# ScreenBase.net
KiCad netlist of a schematic drawn in Altium Designer
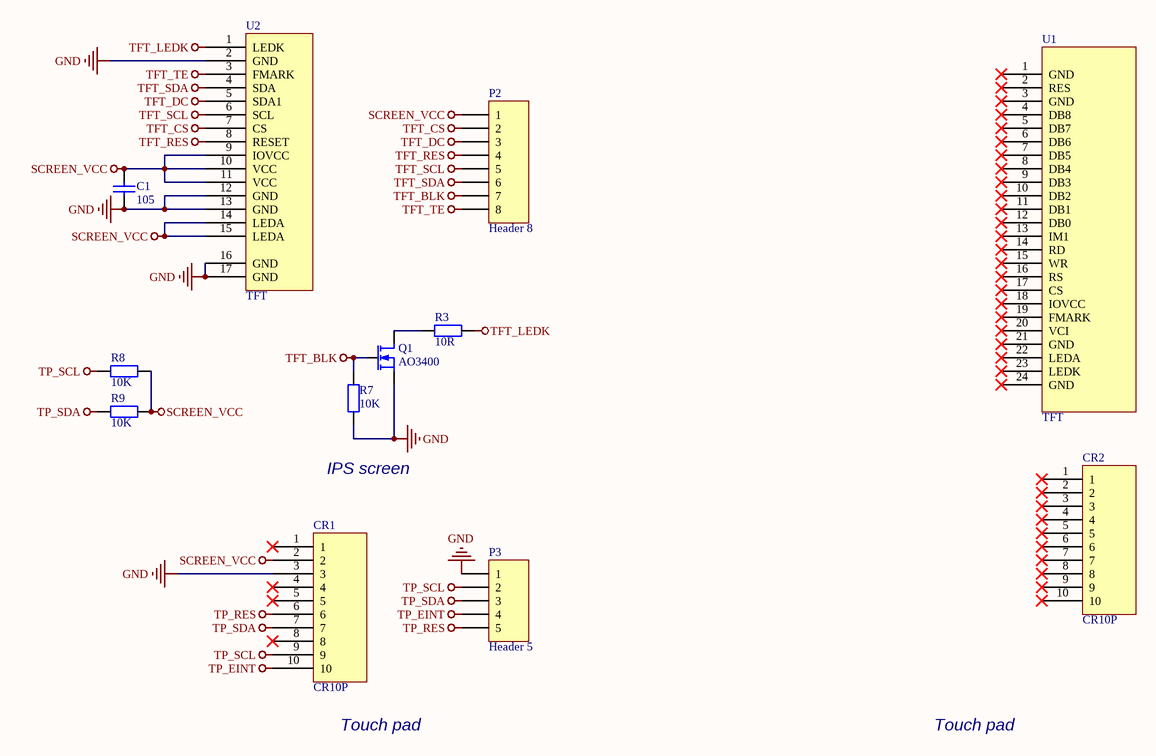
[diagram p0: ScreenBase.SchDoc]

(export (version "E")
  (design (tool "Eeschema 10.0.6"))
  (components
    (comp (ref "C1")
      (value "105")
      (footprint "电容_C0603")
      (fields (field (name "C") "105"))
      (libsource (lib "元件库") (part "cap"))
    )
    (comp (ref "CR1")
      (value "CR10P")
      (footprint "TriggersLib:CONN RCPT 10POS 0.4MM")
      (description "板对板连接器")
      (libsource (lib "TriggersLib") (part "CONN RCPT 10P"))
    )
    (comp (ref "CR2")
      (value "CR10P")
      (footprint "TriggersLib:CONN RCPT 10POS 0.4MM")
      (description "板对板连接器")
      (libsource (lib "TriggersLib") (part "CONN RCPT 10P"))
    )
    (comp (ref "P2")
      (value "Header 8")
      (footprint "HDR1X8")
      (description "Header, 8-Pin")
      (fields (field (name "PUBLISHER") "Altium Limited"))
      (libsource (lib "Miscellaneous Connectors") (part "Header 8"))
    )
    (comp (ref "P3")
      (value "Header 5")
      (footprint "HDR1X5")
      (description "Header, 5-Pin")
      (fields (field (name "PUBLISHER") "Altium Limited"))
      (libsource (lib "Miscellaneous Connectors") (part "Header 5"))
    )
    (comp (ref "Q1")
      (value "AO3400")
      (footprint "MOS_SOT-23")
      (fields (field (name "_MODEL") "AO3400"))
      (libsource (lib "元件库") (part "MOSFET-N"))
    )
    (comp (ref "R3")
      (value "10R")
      (footprint "电阻_R0603")
      (fields (field (name "_VALUE") "10R"))
      (libsource (lib "") (part "Res_1"))
    )
    (comp (ref "R7")
      (value "10K")
      (footprint "电阻_R0603")
      (fields (field (name "_VALUE") "10K"))
      (libsource (lib "") (part "Res_2"))
    )
    (comp (ref "R8")
      (value "10K")
      (footprint "电阻_R0603")
      (fields (field (name "_VALUE") "10K"))
      (libsource (lib "元件库") (part "Res"))
    )
    (comp (ref "R9")
      (value "10K")
      (footprint "电阻_R0603")
      (fields (field (name "_VALUE") "10K"))
      (libsource (lib "元件库") (part "Res"))
    )
    (comp (ref "U1")
      (value "TFT")
      (footprint "TriggersLib:CONN-SMD_DF37NC-24DS-0.4V(51)")
      (libsource (lib "TriggersLib") (part "TFT_IPS_8Bit_1.54_240*240"))
    )
    (comp (ref "U2")
      (value "TFT")
      (footprint "TriggersLib:FPC-0.30mm-15P")
      (description "IPS电容式触摸屏")
      (libsource (lib "TriggersLib") (part "TFT_IPS1-1.54寸240*240-AML015410V1"))
    )
  )
  (nets
    (net (code "1") (name "GND") (class "Default")
      (node (ref "C1") (pin "2") (pinfunction "2_2") (pintype "passive"))
      (node (ref "CR1") (pin "3") (pinfunction "3_3") (pintype "passive"))
      (node (ref "P3") (pin "1") (pinfunction "1_1") (pintype "passive"))
      (node (ref "Q1") (pin "3") (pinfunction "S_3") (pintype "passive"))
      (node (ref "R7") (pin "1") (pinfunction "1_1") (pintype "passive"))
      (node (ref "U2") (pin "12") (pinfunction "GND_12") (pintype "passive"))
      (node (ref "U2") (pin "13") (pinfunction "GND_13") (pintype "passive"))
      (node (ref "U2") (pin "16") (pinfunction "GND_16") (pintype "passive"))
      (node (ref "U2") (pin "17") (pinfunction "GND_17") (pintype "passive"))
      (node (ref "U2") (pin "2") (pinfunction "GND_2") (pintype "passive"))
    )
    (net (code "2") (name "Net-(Q1-D)") (class "Default")
      (node (ref "Q1") (pin "2") (pinfunction "D_2") (pintype "passive"))
      (node (ref "R3") (pin "1") (pinfunction "1_1") (pintype "passive"))
    )
    (net (code "3") (name "SCREEN_VCC") (class "Default")
      (node (ref "C1") (pin "1") (pinfunction "1_1") (pintype "passive"))
      (node (ref "CR1") (pin "2") (pinfunction "2_2") (pintype "passive"))
      (node (ref "P2") (pin "1") (pinfunction "1_1") (pintype "passive"))
      (node (ref "R8") (pin "1") (pinfunction "1_1") (pintype "passive"))
      (node (ref "R9") (pin "1") (pinfunction "1_1") (pintype "passive"))
      (node (ref "U2") (pin "10") (pinfunction "VCC_10") (pintype "passive"))
      (node (ref "U2") (pin "11") (pinfunction "VCC_11") (pintype "passive"))
      (node (ref "U2") (pin "14") (pinfunction "LEDA_14") (pintype "passive"))
      (node (ref "U2") (pin "15") (pinfunction "LEDA_15") (pintype "passive"))
      (node (ref "U2") (pin "9") (pinfunction "IOVCC_9") (pintype "passive"))
    )
    (net (code "4") (name "TFT_BLK") (class "Default")
      (node (ref "P2") (pin "7") (pinfunction "7_7") (pintype "passive"))
      (node (ref "Q1") (pin "1") (pinfunction "G_1") (pintype "passive"))
      (node (ref "R7") (pin "2") (pinfunction "2_2") (pintype "passive"))
    )
    (net (code "5") (name "TFT_CS") (class "Default")
      (node (ref "P2") (pin "2") (pinfunction "2_2") (pintype "passive"))
      (node (ref "U2") (pin "7") (pinfunction "CS_7") (pintype "passive"))
    )
    (net (code "6") (name "TFT_DC") (class "Default")
      (node (ref "P2") (pin "3") (pinfunction "3_3") (pintype "passive"))
      (node (ref "U2") (pin "5") (pinfunction "SDA1_5") (pintype "passive"))
    )
    (net (code "7") (name "TFT_LEDK") (class "Default")
      (node (ref "R3") (pin "2") (pinfunction "2_2") (pintype "passive"))
      (node (ref "U2") (pin "1") (pinfunction "LEDK_1") (pintype "passive"))
    )
    (net (code "8") (name "TFT_RES") (class "Default")
      (node (ref "P2") (pin "4") (pinfunction "4_4") (pintype "passive"))
      (node (ref "U2") (pin "8") (pinfunction "RESET_8") (pintype "passive"))
    )
    (net (code "9") (name "TFT_SCL") (class "Default")
      (node (ref "P2") (pin "5") (pinfunction "5_5") (pintype "passive"))
      (node (ref "U2") (pin "6") (pinfunction "SCL_6") (pintype "passive"))
    )
    (net (code "10") (name "TFT_SDA") (class "Default")
      (node (ref "P2") (pin "6") (pinfunction "6_6") (pintype "passive"))
      (node (ref "U2") (pin "4") (pinfunction "SDA_4") (pintype "passive"))
    )
    (net (code "11") (name "TFT_TE") (class "Default")
      (node (ref "P2") (pin "8") (pinfunction "8_8") (pintype "passive"))
      (node (ref "U2") (pin "3") (pinfunction "FMARK_3") (pintype "passive"))
    )
    (net (code "12") (name "TP_EINT") (class "Default")
      (node (ref "CR1") (pin "10") (pinfunction "10_10") (pintype "passive"))
      (node (ref "P3") (pin "4") (pinfunction "4_4") (pintype "passive"))
    )
    (net (code "13") (name "TP_RES") (class "Default")
      (node (ref "CR1") (pin "6") (pinfunction "6_6") (pintype "passive"))
      (node (ref "P3") (pin "5") (pinfunction "5_5") (pintype "passive"))
    )
    (net (code "14") (name "TP_SCL") (class "Default")
      (node (ref "CR1") (pin "9") (pinfunction "9_9") (pintype "passive"))
      (node (ref "P3") (pin "2") (pinfunction "2_2") (pintype "passive"))
      (node (ref "R8") (pin "2") (pinfunction "2_2") (pintype "passive"))
    )
    (net (code "15") (name "TP_SDA") (class "Default")
      (node (ref "CR1") (pin "7") (pinfunction "7_7") (pintype "passive"))
      (node (ref "P3") (pin "3") (pinfunction "3_3") (pintype "passive"))
      (node (ref "R9") (pin "2") (pinfunction "2_2") (pintype "passive"))
    )
    (net (code "16") (name "unconnected-(CR1-Pad1)") (class "Default")
      (node (ref "CR1") (pin "1") (pinfunction "1_1") (pintype "passive+no_connect"))
    )
    (net (code "17") (name "unconnected-(CR1-Pad4)") (class "Default")
      (node (ref "CR1") (pin "4") (pinfunction "4_4") (pintype "passive+no_connect"))
    )
    (net (code "18") (name "unconnected-(CR1-Pad5)") (class "Default")
      (node (ref "CR1") (pin "5") (pinfunction "5_5") (pintype "passive+no_connect"))
    )
    (net (code "19") (name "unconnected-(CR1-Pad8)") (class "Default")
      (node (ref "CR1") (pin "8") (pinfunction "8_8") (pintype "passive+no_connect"))
    )
    (net (code "20") (name "unconnected-(CR2-Pad1)") (class "Default")
      (node (ref "CR2") (pin "1") (pinfunction "1_1") (pintype "passive+no_connect"))
    )
    (net (code "21") (name "unconnected-(CR2-Pad2)") (class "Default")
      (node (ref "CR2") (pin "2") (pinfunction "2_2") (pintype "passive+no_connect"))
    )
    (net (code "22") (name "unconnected-(CR2-Pad3)") (class "Default")
      (node (ref "CR2") (pin "3") (pinfunction "3_3") (pintype "passive+no_connect"))
    )
    (net (code "23") (name "unconnected-(CR2-Pad4)") (class "Default")
      (node (ref "CR2") (pin "4") (pinfunction "4_4") (pintype "passive+no_connect"))
    )
    (net (code "24") (name "unconnected-(CR2-Pad5)") (class "Default")
      (node (ref "CR2") (pin "5") (pinfunction "5_5") (pintype "passive+no_connect"))
    )
    (net (code "25") (name "unconnected-(CR2-Pad6)") (class "Default")
      (node (ref "CR2") (pin "6") (pinfunction "6_6") (pintype "passive+no_connect"))
    )
    (net (code "26") (name "unconnected-(CR2-Pad7)") (class "Default")
      (node (ref "CR2") (pin "7") (pinfunction "7_7") (pintype "passive+no_connect"))
    )
    (net (code "27") (name "unconnected-(CR2-Pad8)") (class "Default")
      (node (ref "CR2") (pin "8") (pinfunction "8_8") (pintype "passive+no_connect"))
    )
    (net (code "28") (name "unconnected-(CR2-Pad9)") (class "Default")
      (node (ref "CR2") (pin "9") (pinfunction "9_9") (pintype "passive+no_connect"))
    )
    (net (code "29") (name "unconnected-(CR2-Pad10)") (class "Default")
      (node (ref "CR2") (pin "10") (pinfunction "10_10") (pintype "passive+no_connect"))
    )
    (net (code "30") (name "unconnected-(U1-CS-Pad17)") (class "Default")
      (node (ref "U1") (pin "17") (pinfunction "CS_17") (pintype "passive+no_connect"))
    )
    (net (code "31") (name "unconnected-(U1-DB0-Pad12)") (class "Default")
      (node (ref "U1") (pin "12") (pinfunction "DB0_12") (pintype "passive+no_connect"))
    )
    (net (code "32") (name "unconnected-(U1-DB1-Pad11)") (class "Default")
      (node (ref "U1") (pin "11") (pinfunction "DB1_11") (pintype "passive+no_connect"))
    )
    (net (code "33") (name "unconnected-(U1-DB2-Pad10)") (class "Default")
      (node (ref "U1") (pin "10") (pinfunction "DB2_10") (pintype "passive+no_connect"))
    )
    (net (code "34") (name "unconnected-(U1-DB3-Pad9)") (class "Default")
      (node (ref "U1") (pin "9") (pinfunction "DB3_9") (pintype "passive+no_connect"))
    )
    (net (code "35") (name "unconnected-(U1-DB4-Pad8)") (class "Default")
      (node (ref "U1") (pin "8") (pinfunction "DB4_8") (pintype "passive+no_connect"))
    )
    (net (code "36") (name "unconnected-(U1-DB5-Pad7)") (class "Default")
      (node (ref "U1") (pin "7") (pinfunction "DB5_7") (pintype "passive+no_connect"))
    )
    (net (code "37") (name "unconnected-(U1-DB6-Pad6)") (class "Default")
      (node (ref "U1") (pin "6") (pinfunction "DB6_6") (pintype "passive+no_connect"))
    )
    (net (code "38") (name "unconnected-(U1-DB7-Pad5)") (class "Default")
      (node (ref "U1") (pin "5") (pinfunction "DB7_5") (pintype "passive+no_connect"))
    )
    (net (code "39") (name "unconnected-(U1-DB8-Pad4)") (class "Default")
      (node (ref "U1") (pin "4") (pinfunction "DB8_4") (pintype "passive+no_connect"))
    )
    (net (code "40") (name "unconnected-(U1-FMARK-Pad19)") (class "Default")
      (node (ref "U1") (pin "19") (pinfunction "FMARK_19") (pintype "passive+no_connect"))
    )
    (net (code "41") (name "unconnected-(U1-GND-Pad1)") (class "Default")
      (node (ref "U1") (pin "1") (pinfunction "GND_1") (pintype "passive+no_connect"))
    )
    (net (code "42") (name "unconnected-(U1-GND-Pad3)") (class "Default")
      (node (ref "U1") (pin "3") (pinfunction "GND_3") (pintype "passive+no_connect"))
    )
    (net (code "43") (name "unconnected-(U1-GND-Pad21)") (class "Default")
      (node (ref "U1") (pin "21") (pinfunction "GND_21") (pintype "passive+no_connect"))
    )
    (net (code "44") (name "unconnected-(U1-GND-Pad24)") (class "Default")
      (node (ref "U1") (pin "24") (pinfunction "GND_24") (pintype "passive+no_connect"))
    )
    (net (code "45") (name "unconnected-(U1-IM1-Pad13)") (class "Default")
      (node (ref "U1") (pin "13") (pinfunction "IM1_13") (pintype "passive+no_connect"))
    )
    (net (code "46") (name "unconnected-(U1-IOVCC-Pad18)") (class "Default")
      (node (ref "U1") (pin "18") (pinfunction "IOVCC_18") (pintype "passive+no_connect"))
    )
    (net (code "47") (name "unconnected-(U1-LEDA-Pad22)") (class "Default")
      (node (ref "U1") (pin "22") (pinfunction "LEDA_22") (pintype "passive+no_connect"))
    )
    (net (code "48") (name "unconnected-(U1-LEDK-Pad23)") (class "Default")
      (node (ref "U1") (pin "23") (pinfunction "LEDK_23") (pintype "passive+no_connect"))
    )
    (net (code "49") (name "unconnected-(U1-RD-Pad14)") (class "Default")
      (node (ref "U1") (pin "14") (pinfunction "RD_14") (pintype "passive+no_connect"))
    )
    (net (code "50") (name "unconnected-(U1-RES-Pad2)") (class "Default")
      (node (ref "U1") (pin "2") (pinfunction "RES_2") (pintype "passive+no_connect"))
    )
    (net (code "51") (name "unconnected-(U1-RS-Pad16)") (class "Default")
      (node (ref "U1") (pin "16") (pinfunction "RS_16") (pintype "passive+no_connect"))
    )
    (net (code "52") (name "unconnected-(U1-VCI-Pad20)") (class "Default")
      (node (ref "U1") (pin "20") (pinfunction "VCI_20") (pintype "passive+no_connect"))
    )
    (net (code "53") (name "unconnected-(U1-WR-Pad15)") (class "Default")
      (node (ref "U1") (pin "15") (pinfunction "WR_15") (pintype "passive+no_connect"))
    )
  )
)
